# XOR_gate.net
KiCad netlist of a schematic drawn in EAGLE
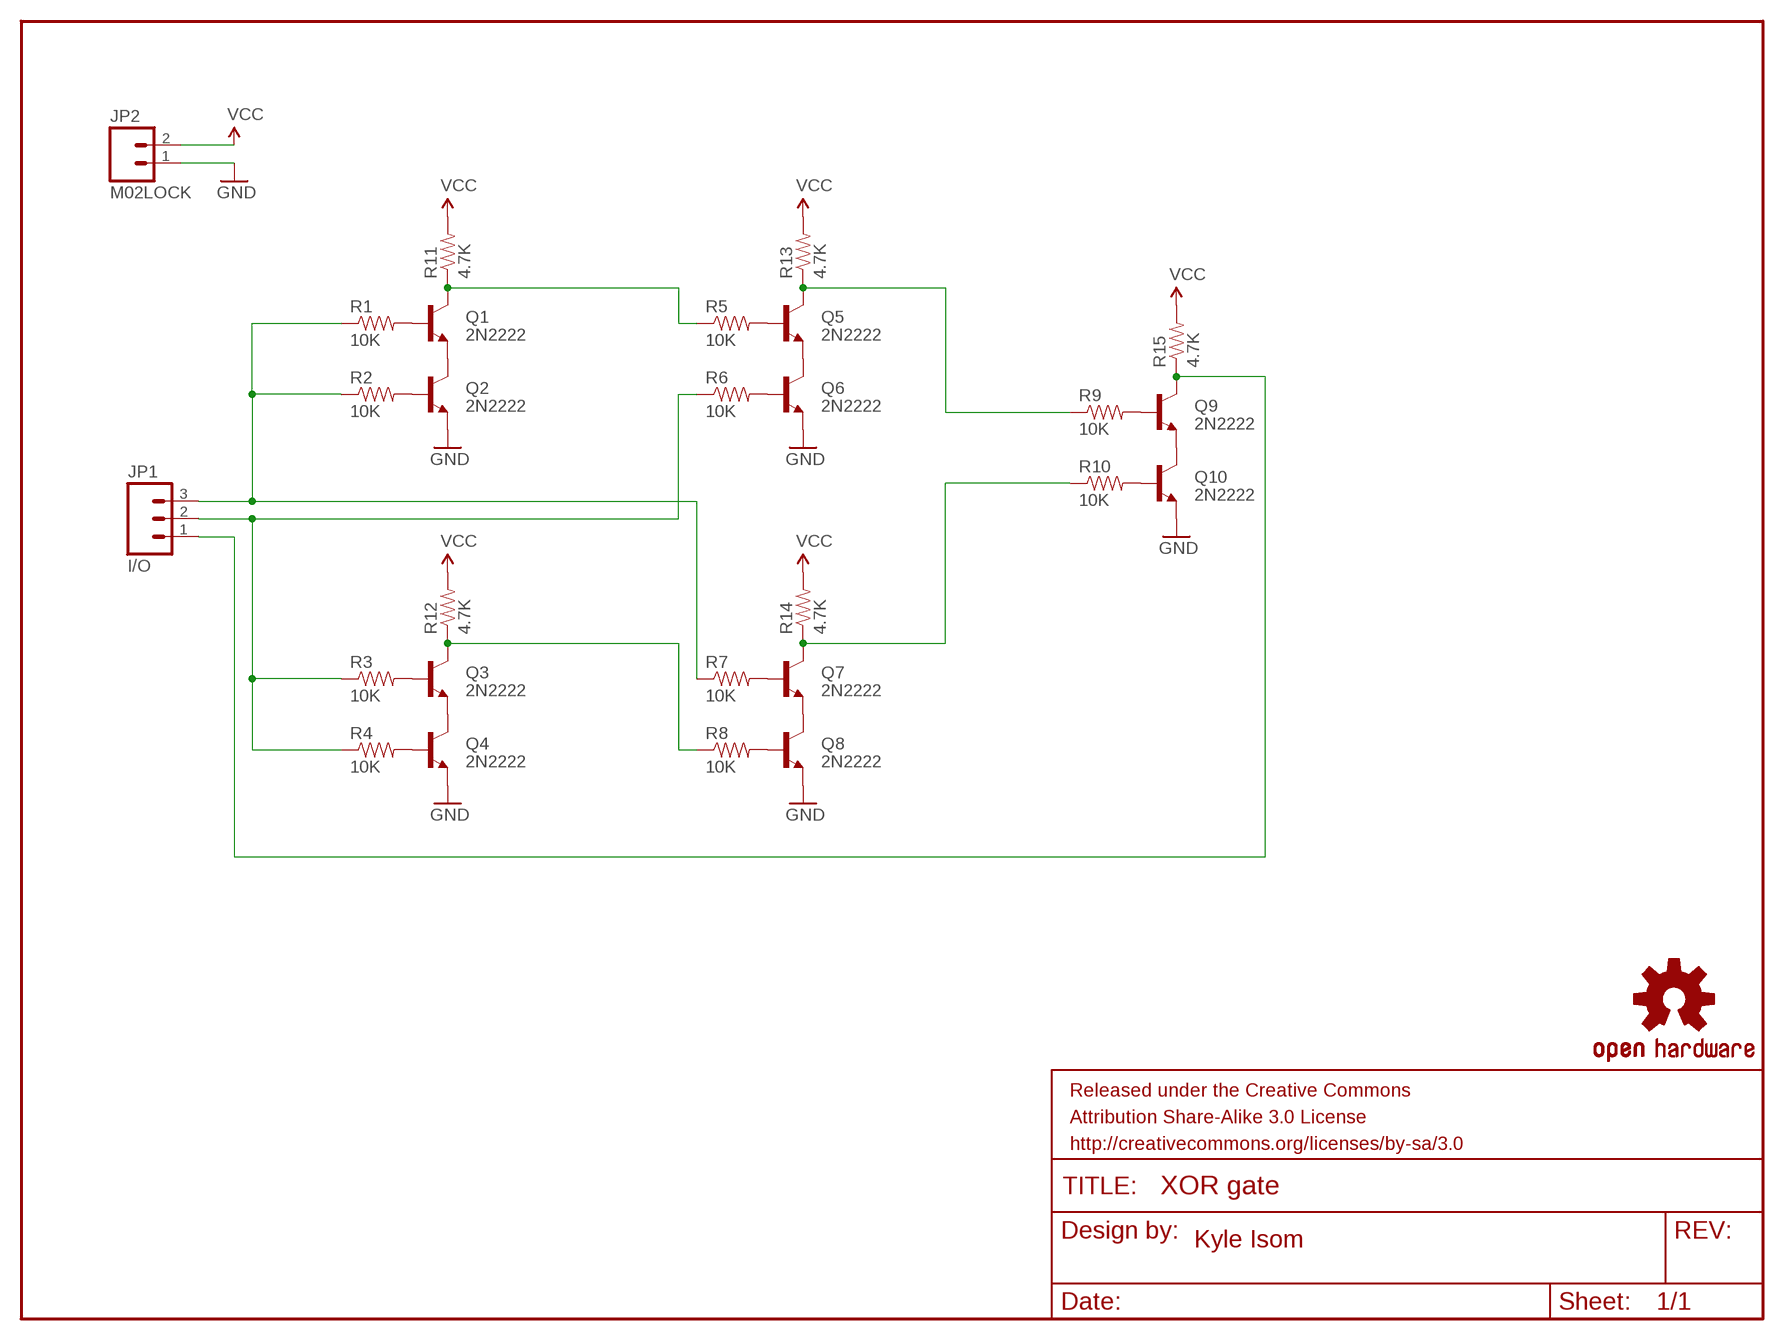
[diagram p0: schematic, sheet 1]

(export (version "E")
  (design (tool "Eeschema 10.0.6"))
  (components
    (comp (ref "FRAME1")
      (value "FRAME-LETTER")
      (footprint "eagle-import:CREATIVE_COMMONS")
      (libsource (lib "eagle-import") (part "FRAME-LETTER"))
    )
    (comp (ref "JP1")
      (value "I/O")
      (footprint "eagle-import:1X03_LOCK")
      (libsource (lib "eagle-import") (part "M03LOCK"))
    )
    (comp (ref "JP2")
      (value "M02LOCK")
      (footprint "eagle-import:1X02_LOCK")
      (libsource (lib "eagle-import") (part "M02LOCK"))
    )
    (comp (ref "LOGO1")
      (value "OSHW-LOGOS")
      (footprint "eagle-import:OSHW-LOGO-S")
      (libsource (lib "eagle-import") (part "OSHW-LOGOS"))
    )
    (comp (ref "Q1")
      (value "2N2222")
      (footprint "eagle-import:TO-92-AMMO")
      (libsource (lib "eagle-import") (part "TRANSISTOR_NPNTO-92-AMMO"))
    )
    (comp (ref "Q2")
      (value "2N2222")
      (footprint "eagle-import:TO-92-AMMO")
      (libsource (lib "eagle-import") (part "TRANSISTOR_NPNTO-92-AMMO"))
    )
    (comp (ref "Q3")
      (value "2N2222")
      (footprint "eagle-import:TO-92-AMMO")
      (libsource (lib "eagle-import") (part "TRANSISTOR_NPNTO-92-AMMO"))
    )
    (comp (ref "Q4")
      (value "2N2222")
      (footprint "eagle-import:TO-92-AMMO")
      (libsource (lib "eagle-import") (part "TRANSISTOR_NPNTO-92-AMMO"))
    )
    (comp (ref "Q5")
      (value "2N2222")
      (footprint "eagle-import:TO-92-AMMO")
      (libsource (lib "eagle-import") (part "TRANSISTOR_NPNTO-92-AMMO"))
    )
    (comp (ref "Q6")
      (value "2N2222")
      (footprint "eagle-import:TO-92-AMMO")
      (libsource (lib "eagle-import") (part "TRANSISTOR_NPNTO-92-AMMO"))
    )
    (comp (ref "Q7")
      (value "2N2222")
      (footprint "eagle-import:TO-92-AMMO")
      (libsource (lib "eagle-import") (part "TRANSISTOR_NPNTO-92-AMMO"))
    )
    (comp (ref "Q8")
      (value "2N2222")
      (footprint "eagle-import:TO-92-AMMO")
      (libsource (lib "eagle-import") (part "TRANSISTOR_NPNTO-92-AMMO"))
    )
    (comp (ref "Q9")
      (value "2N2222")
      (footprint "eagle-import:TO-92-AMMO")
      (libsource (lib "eagle-import") (part "TRANSISTOR_NPNTO-92-AMMO"))
    )
    (comp (ref "Q10")
      (value "2N2222")
      (footprint "eagle-import:TO-92-AMMO")
      (libsource (lib "eagle-import") (part "TRANSISTOR_NPNTO-92-AMMO"))
    )
    (comp (ref "R1")
      (value "10K")
      (footprint "eagle-import:AXIAL-0.4")
      (libsource (lib "eagle-import") (part "RESISTORPTH-1/4W"))
    )
    (comp (ref "R2")
      (value "10K")
      (footprint "eagle-import:AXIAL-0.4")
      (libsource (lib "eagle-import") (part "RESISTORPTH-1/4W"))
    )
    (comp (ref "R3")
      (value "10K")
      (footprint "eagle-import:AXIAL-0.4")
      (libsource (lib "eagle-import") (part "RESISTORPTH-1/4W"))
    )
    (comp (ref "R4")
      (value "10K")
      (footprint "eagle-import:AXIAL-0.4")
      (libsource (lib "eagle-import") (part "RESISTORPTH-1/4W"))
    )
    (comp (ref "R5")
      (value "10K")
      (footprint "eagle-import:AXIAL-0.4")
      (libsource (lib "eagle-import") (part "RESISTORPTH-1/4W"))
    )
    (comp (ref "R6")
      (value "10K")
      (footprint "eagle-import:AXIAL-0.4")
      (libsource (lib "eagle-import") (part "RESISTORPTH-1/4W"))
    )
    (comp (ref "R7")
      (value "10K")
      (footprint "eagle-import:AXIAL-0.4")
      (libsource (lib "eagle-import") (part "RESISTORPTH-1/4W"))
    )
    (comp (ref "R8")
      (value "10K")
      (footprint "eagle-import:AXIAL-0.4")
      (libsource (lib "eagle-import") (part "RESISTORPTH-1/4W"))
    )
    (comp (ref "R9")
      (value "10K")
      (footprint "eagle-import:AXIAL-0.4")
      (libsource (lib "eagle-import") (part "RESISTORPTH-1/4W"))
    )
    (comp (ref "R10")
      (value "10K")
      (footprint "eagle-import:AXIAL-0.4")
      (libsource (lib "eagle-import") (part "RESISTORPTH-1/4W"))
    )
    (comp (ref "R11")
      (value "4.7K")
      (footprint "eagle-import:AXIAL-0.4")
      (libsource (lib "eagle-import") (part "RESISTORPTH-1/4W"))
    )
    (comp (ref "R12")
      (value "4.7K")
      (footprint "eagle-import:AXIAL-0.4")
      (libsource (lib "eagle-import") (part "RESISTORPTH-1/4W"))
    )
    (comp (ref "R13")
      (value "4.7K")
      (footprint "eagle-import:AXIAL-0.4")
      (libsource (lib "eagle-import") (part "RESISTORPTH-1/4W"))
    )
    (comp (ref "R14")
      (value "4.7K")
      (footprint "eagle-import:AXIAL-0.4")
      (libsource (lib "eagle-import") (part "RESISTORPTH-1/4W"))
    )
    (comp (ref "R15")
      (value "4.7K")
      (footprint "eagle-import:AXIAL-0.4")
      (libsource (lib "eagle-import") (part "RESISTORPTH-1/4W"))
    )
  )
  (nets
    (net (code "1") (name "GND") (class "Default")
      (node (ref "JP2") (pin "1") (pinfunction "1_1") (pintype "passive"))
      (node (ref "Q10") (pin "1") (pinfunction "E_1") (pintype "passive"))
      (node (ref "Q2") (pin "1") (pinfunction "E_1") (pintype "passive"))
      (node (ref "Q4") (pin "1") (pinfunction "E_1") (pintype "passive"))
      (node (ref "Q6") (pin "1") (pinfunction "E_1") (pintype "passive"))
      (node (ref "Q8") (pin "1") (pinfunction "E_1") (pintype "passive"))
    )
    (net (code "2") (name "Net-(Q1-B)") (class "Default")
      (node (ref "Q1") (pin "2") (pinfunction "B_2") (pintype "passive"))
      (node (ref "R1") (pin "P$2") (pinfunction "2_P$2") (pintype "passive"))
    )
    (net (code "3") (name "Net-(Q1-C)") (class "Default")
      (node (ref "Q1") (pin "3") (pinfunction "C_3") (pintype "passive"))
      (node (ref "R11") (pin "P$1") (pinfunction "1_P$1") (pintype "passive"))
      (node (ref "R5") (pin "P$1") (pinfunction "1_P$1") (pintype "passive"))
    )
    (net (code "4") (name "Net-(Q1-E)") (class "Default")
      (node (ref "Q1") (pin "1") (pinfunction "E_1") (pintype "passive"))
      (node (ref "Q2") (pin "3") (pinfunction "C_3") (pintype "passive"))
    )
    (net (code "5") (name "Net-(Q2-B)") (class "Default")
      (node (ref "Q2") (pin "2") (pinfunction "B_2") (pintype "passive"))
      (node (ref "R2") (pin "P$2") (pinfunction "2_P$2") (pintype "passive"))
    )
    (net (code "6") (name "Net-(Q3-B)") (class "Default")
      (node (ref "Q3") (pin "2") (pinfunction "B_2") (pintype "passive"))
      (node (ref "R3") (pin "P$2") (pinfunction "2_P$2") (pintype "passive"))
    )
    (net (code "7") (name "Net-(Q3-C)") (class "Default")
      (node (ref "Q3") (pin "3") (pinfunction "C_3") (pintype "passive"))
      (node (ref "R12") (pin "P$1") (pinfunction "1_P$1") (pintype "passive"))
      (node (ref "R8") (pin "P$1") (pinfunction "1_P$1") (pintype "passive"))
    )
    (net (code "8") (name "Net-(Q3-E)") (class "Default")
      (node (ref "Q3") (pin "1") (pinfunction "E_1") (pintype "passive"))
      (node (ref "Q4") (pin "3") (pinfunction "C_3") (pintype "passive"))
    )
    (net (code "9") (name "Net-(Q4-B)") (class "Default")
      (node (ref "Q4") (pin "2") (pinfunction "B_2") (pintype "passive"))
      (node (ref "R4") (pin "P$2") (pinfunction "2_P$2") (pintype "passive"))
    )
    (net (code "10") (name "Net-(Q5-B)") (class "Default")
      (node (ref "Q5") (pin "2") (pinfunction "B_2") (pintype "passive"))
      (node (ref "R5") (pin "P$2") (pinfunction "2_P$2") (pintype "passive"))
    )
    (net (code "11") (name "Net-(Q5-C)") (class "Default")
      (node (ref "Q5") (pin "3") (pinfunction "C_3") (pintype "passive"))
      (node (ref "R13") (pin "P$1") (pinfunction "1_P$1") (pintype "passive"))
      (node (ref "R9") (pin "P$1") (pinfunction "1_P$1") (pintype "passive"))
    )
    (net (code "12") (name "Net-(Q5-E)") (class "Default")
      (node (ref "Q5") (pin "1") (pinfunction "E_1") (pintype "passive"))
      (node (ref "Q6") (pin "3") (pinfunction "C_3") (pintype "passive"))
    )
    (net (code "13") (name "Net-(Q6-B)") (class "Default")
      (node (ref "Q6") (pin "2") (pinfunction "B_2") (pintype "passive"))
      (node (ref "R6") (pin "P$2") (pinfunction "2_P$2") (pintype "passive"))
    )
    (net (code "14") (name "Net-(Q7-B)") (class "Default")
      (node (ref "Q7") (pin "2") (pinfunction "B_2") (pintype "passive"))
      (node (ref "R7") (pin "P$2") (pinfunction "2_P$2") (pintype "passive"))
    )
    (net (code "15") (name "Net-(Q7-C)") (class "Default")
      (node (ref "Q7") (pin "3") (pinfunction "C_3") (pintype "passive"))
      (node (ref "R10") (pin "P$1") (pinfunction "1_P$1") (pintype "passive"))
      (node (ref "R14") (pin "P$1") (pinfunction "1_P$1") (pintype "passive"))
    )
    (net (code "16") (name "Net-(Q7-E)") (class "Default")
      (node (ref "Q7") (pin "1") (pinfunction "E_1") (pintype "passive"))
      (node (ref "Q8") (pin "3") (pinfunction "C_3") (pintype "passive"))
    )
    (net (code "17") (name "Net-(Q8-B)") (class "Default")
      (node (ref "Q8") (pin "2") (pinfunction "B_2") (pintype "passive"))
      (node (ref "R8") (pin "P$2") (pinfunction "2_P$2") (pintype "passive"))
    )
    (net (code "18") (name "Net-(Q9-B)") (class "Default")
      (node (ref "Q9") (pin "2") (pinfunction "B_2") (pintype "passive"))
      (node (ref "R9") (pin "P$2") (pinfunction "2_P$2") (pintype "passive"))
    )
    (net (code "19") (name "Net-(Q9-C)") (class "Default")
      (node (ref "JP1") (pin "1") (pinfunction "1_1") (pintype "passive"))
      (node (ref "Q9") (pin "3") (pinfunction "C_3") (pintype "passive"))
      (node (ref "R15") (pin "P$1") (pinfunction "1_P$1") (pintype "passive"))
    )
    (net (code "20") (name "Net-(Q10-B)") (class "Default")
      (node (ref "Q10") (pin "2") (pinfunction "B_2") (pintype "passive"))
      (node (ref "R10") (pin "P$2") (pinfunction "2_P$2") (pintype "passive"))
    )
    (net (code "21") (name "Net-(Q10-C)") (class "Default")
      (node (ref "Q10") (pin "3") (pinfunction "C_3") (pintype "passive"))
      (node (ref "Q9") (pin "1") (pinfunction "E_1") (pintype "passive"))
    )
    (net (code "22") (name "Net-(R1-1)") (class "Default")
      (node (ref "JP1") (pin "3") (pinfunction "3_3") (pintype "passive"))
      (node (ref "R1") (pin "P$1") (pinfunction "1_P$1") (pintype "passive"))
      (node (ref "R2") (pin "P$1") (pinfunction "1_P$1") (pintype "passive"))
      (node (ref "R7") (pin "P$1") (pinfunction "1_P$1") (pintype "passive"))
    )
    (net (code "23") (name "Net-(R3-1)") (class "Default")
      (node (ref "JP1") (pin "2") (pinfunction "2_2") (pintype "passive"))
      (node (ref "R3") (pin "P$1") (pinfunction "1_P$1") (pintype "passive"))
      (node (ref "R4") (pin "P$1") (pinfunction "1_P$1") (pintype "passive"))
      (node (ref "R6") (pin "P$1") (pinfunction "1_P$1") (pintype "passive"))
    )
    (net (code "24") (name "VCC") (class "Default")
      (node (ref "JP2") (pin "2") (pinfunction "2_2") (pintype "passive"))
      (node (ref "R11") (pin "P$2") (pinfunction "2_P$2") (pintype "passive"))
      (node (ref "R12") (pin "P$2") (pinfunction "2_P$2") (pintype "passive"))
      (node (ref "R13") (pin "P$2") (pinfunction "2_P$2") (pintype "passive"))
      (node (ref "R14") (pin "P$2") (pinfunction "2_P$2") (pintype "passive"))
      (node (ref "R15") (pin "P$2") (pinfunction "2_P$2") (pintype "passive"))
    )
  )
)
